# Encoder.net
KiCad netlist of a schematic drawn in Altium Designer
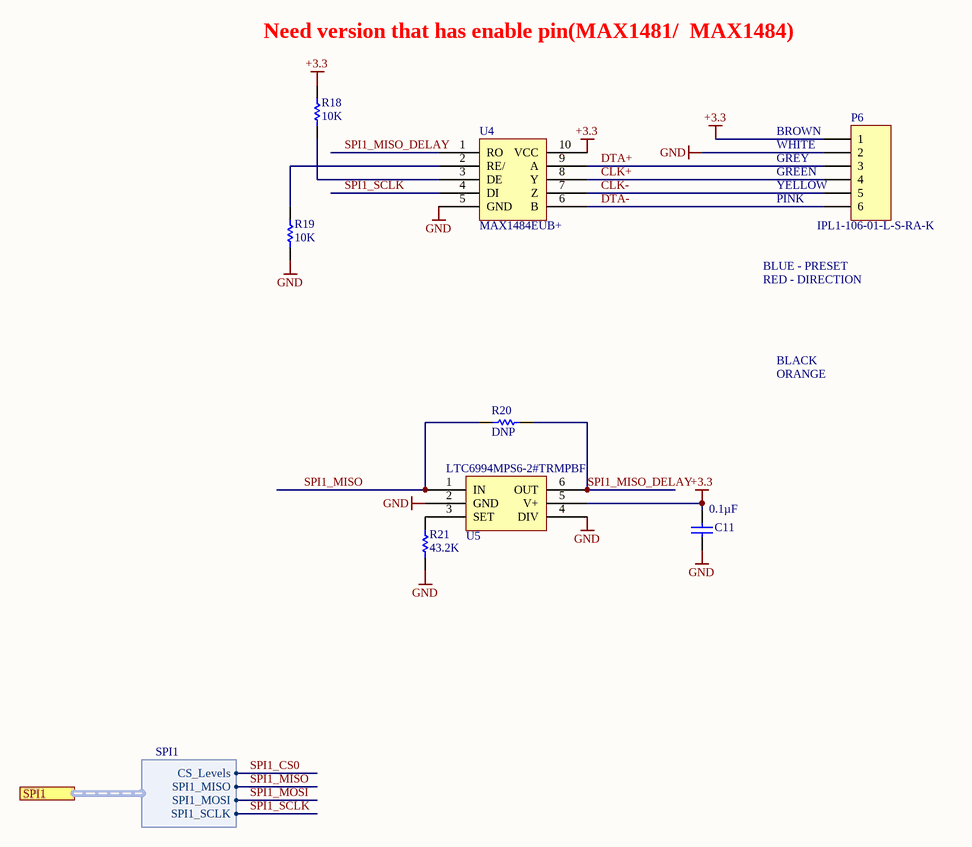
[diagram p0: Encoder.SchDoc]

(export (version "E")
  (design (tool "Eeschema 10.0.6"))
  (components
    (comp (ref "C11")
      (value "CAP CER 0.1UF 25V X7R 0805")
      (footprint "CAPC0805(2012)145_N")
      (fields
        (field (name "MANUFACTURER") "Murata Electronics North America")
        (field (name "MANUFACTURER PART NUMBER") "GRM21BR71E104KA01L")
        (field (name "CAPACITANCE") "0.1µF")
        (field (name "TOLERANCE") "±10%")
      )
      (libsource (lib "Altium Content Vault") (part "CMP-1036-04795-1"))
    )
    (comp (ref "P6")
      (value "IPL1-106-01-L-S-RA-K")
      (footprint "IPL1-106-01-L-S-RA-K")
      (description "Header, 6-Pin")
      (fields (field (name "MANUFACTURER") "Samtec Inc."))
      (libsource (lib "Miscellaneous Connectors") (part "Header 6"))
    )
    (comp (ref "R18")
      (value "10K")
      (footprint "RESC0805(2012)_L")
      (description "RES SMD 10K OHM 1% 1/8W 0805")
      (fields
        (field (name "MANUFACTURER") "Vishay Dale")
        (field (name "MANUFACTURER PART NUMBER") "CRCW080510K0FKEA")
      )
      (libsource (lib "Altium Content Vault") (part "CMP-1013-00215-1"))
    )
    (comp (ref "R19")
      (value "10K")
      (footprint "RESC0805(2012)_L")
      (description "RES SMD 10K OHM 1% 1/8W 0805")
      (fields
        (field (name "MANUFACTURER") "Vishay Dale")
        (field (name "MANUFACTURER PART NUMBER") "CRCW080510K0FKEA")
      )
      (libsource (lib "Altium Content Vault") (part "CMP-1013-00215-1"))
    )
    (comp (ref "R20")
      (value "DNP")
      (footprint "RESC0805(2012)_L")
      (description "RES SMD 0 OHM 5% 1/8W 0805")
      (libsource (lib "Altium Content Vault") (part "CMP-1013-00215-1"))
    )
    (comp (ref "R21")
      (value "43.2K")
      (footprint "RESC0805(2012)_L")
      (description "RES SMD 43.2K OHM 1% 1/8W 0805")
      (fields
        (field (name "MANUFACTURER") "Vishay Dale")
        (field (name "MANUFACTURER PART NUMBER") "CRCW080543K2FKEA")
      )
      (libsource (lib "Altium Content Vault") (part "CMP-1013-00215-1"))
    )
    (comp (ref "U4")
      (value "MAX1484EUB+")
      (footprint "MAX1484EUB+")
      (description "IC TXRX RS485/RS422 10-UMAX")
      (fields (field (name "MANUFACTURER") "Maxim Integrated") (field (name "BASE PART NUMBER") "MAX1484"))
      (libsource (lib "ZLS_Schematic_lib") (part "MAX1484EUB+"))
    )
    (comp (ref "U5")
      (value "LTC6994MPS6-2#TRMPBF")
      (footprint "LTC6994MPS6-2#TRMPBF")
      (fields
        (field (name "MANUFACTURER") "Linear Technology/Analog Devices")
        (field (name "MANUFACTURER PART NUMBER") "LTC6994CS6-2#TRMPBF")
        (field (name "BASE PART NUMBER") "LTC6994")
      )
      (libsource (lib "ZLS_Schematic_lib") (part "LTC6994MPS6-2#TRMPBF"))
    )
  )
  (nets
    (net (code "2") (name "+3.3") (class "Default")
      (node (ref "C11") (pin "1") (pinfunction "1_1") (pintype "passive"))
      (node (ref "P6") (pin "1") (pinfunction "1_1") (pintype "passive"))
      (node (ref "R18") (pin "2") (pinfunction "2_2") (pintype "passive"))
      (node (ref "U4") (pin "10") (pinfunction "VCC_10") (pintype "passive"))
      (node (ref "U5") (pin "5") (pinfunction "V+_5") (pintype "passive"))
    )
    (net (code "3") (name "/CLK+") (class "Default")
      (node (ref "P6") (pin "4") (pinfunction "4_4") (pintype "passive"))
      (node (ref "U4") (pin "8") (pinfunction "Y_8") (pintype "passive"))
    )
    (net (code "4") (name "/CLK-") (class "Default")
      (node (ref "P6") (pin "5") (pinfunction "5_5") (pintype "passive"))
      (node (ref "U4") (pin "7") (pinfunction "Z_7") (pintype "passive"))
    )
    (net (code "5") (name "/DTA+") (class "Default")
      (node (ref "P6") (pin "3") (pinfunction "3_3") (pintype "passive"))
      (node (ref "U4") (pin "9") (pinfunction "A_9") (pintype "passive"))
    )
    (net (code "6") (name "/DTA-") (class "Default")
      (node (ref "P6") (pin "6") (pinfunction "6_6") (pintype "passive"))
      (node (ref "U4") (pin "6") (pinfunction "B_6") (pintype "passive"))
    )
    (net (code "8") (name "/SPI1_MISO") (class "Default")
      (node (ref "R20") (pin "1") (pinfunction "1_1") (pintype "passive"))
      (node (ref "U5") (pin "1") (pinfunction "IN_1") (pintype "passive"))
    )
    (net (code "9") (name "/SPI1_MISO_DELAY") (class "Default")
      (node (ref "R20") (pin "2") (pinfunction "2_2") (pintype "passive"))
      (node (ref "U4") (pin "1") (pinfunction "RO_1") (pintype "passive"))
      (node (ref "U5") (pin "6") (pinfunction "OUT_6") (pintype "passive"))
    )
    (net (code "11") (name "/SPI1_SCLK") (class "Default")
      (node (ref "U4") (pin "4") (pinfunction "DI_4") (pintype "passive"))
    )
    (net (code "13") (name "GND") (class "Default")
      (node (ref "C11") (pin "2") (pinfunction "2_2") (pintype "passive"))
      (node (ref "P6") (pin "2") (pinfunction "2_2") (pintype "passive"))
      (node (ref "R19") (pin "1") (pinfunction "1_1") (pintype "passive"))
      (node (ref "R21") (pin "2") (pinfunction "2_2") (pintype "passive"))
      (node (ref "U4") (pin "5") (pinfunction "GND_5") (pintype "passive"))
      (node (ref "U5") (pin "2") (pinfunction "GND_2") (pintype "passive"))
      (node (ref "U5") (pin "4") (pinfunction "DIV_4") (pintype "passive"))
    )
    (net (code "14") (name "Net-(U4-DE)") (class "Default")
      (node (ref "R18") (pin "1") (pinfunction "1_1") (pintype "passive"))
      (node (ref "U4") (pin "3") (pinfunction "DE_3") (pintype "passive"))
    )
    (net (code "15") (name "Net-(U4-RE{slash})") (class "Default")
      (node (ref "R19") (pin "2") (pinfunction "2_2") (pintype "passive"))
      (node (ref "U4") (pin "2") (pinfunction "RE/_2") (pintype "passive"))
    )
    (net (code "16") (name "Net-(U5-SET)") (class "Default")
      (node (ref "R21") (pin "1") (pinfunction "1_1") (pintype "passive"))
      (node (ref "U5") (pin "3") (pinfunction "SET_3") (pintype "passive"))
    )
  )
)
